# Wattuino-Uno_v10.net
KiCad netlist of a schematic drawn in EAGLE
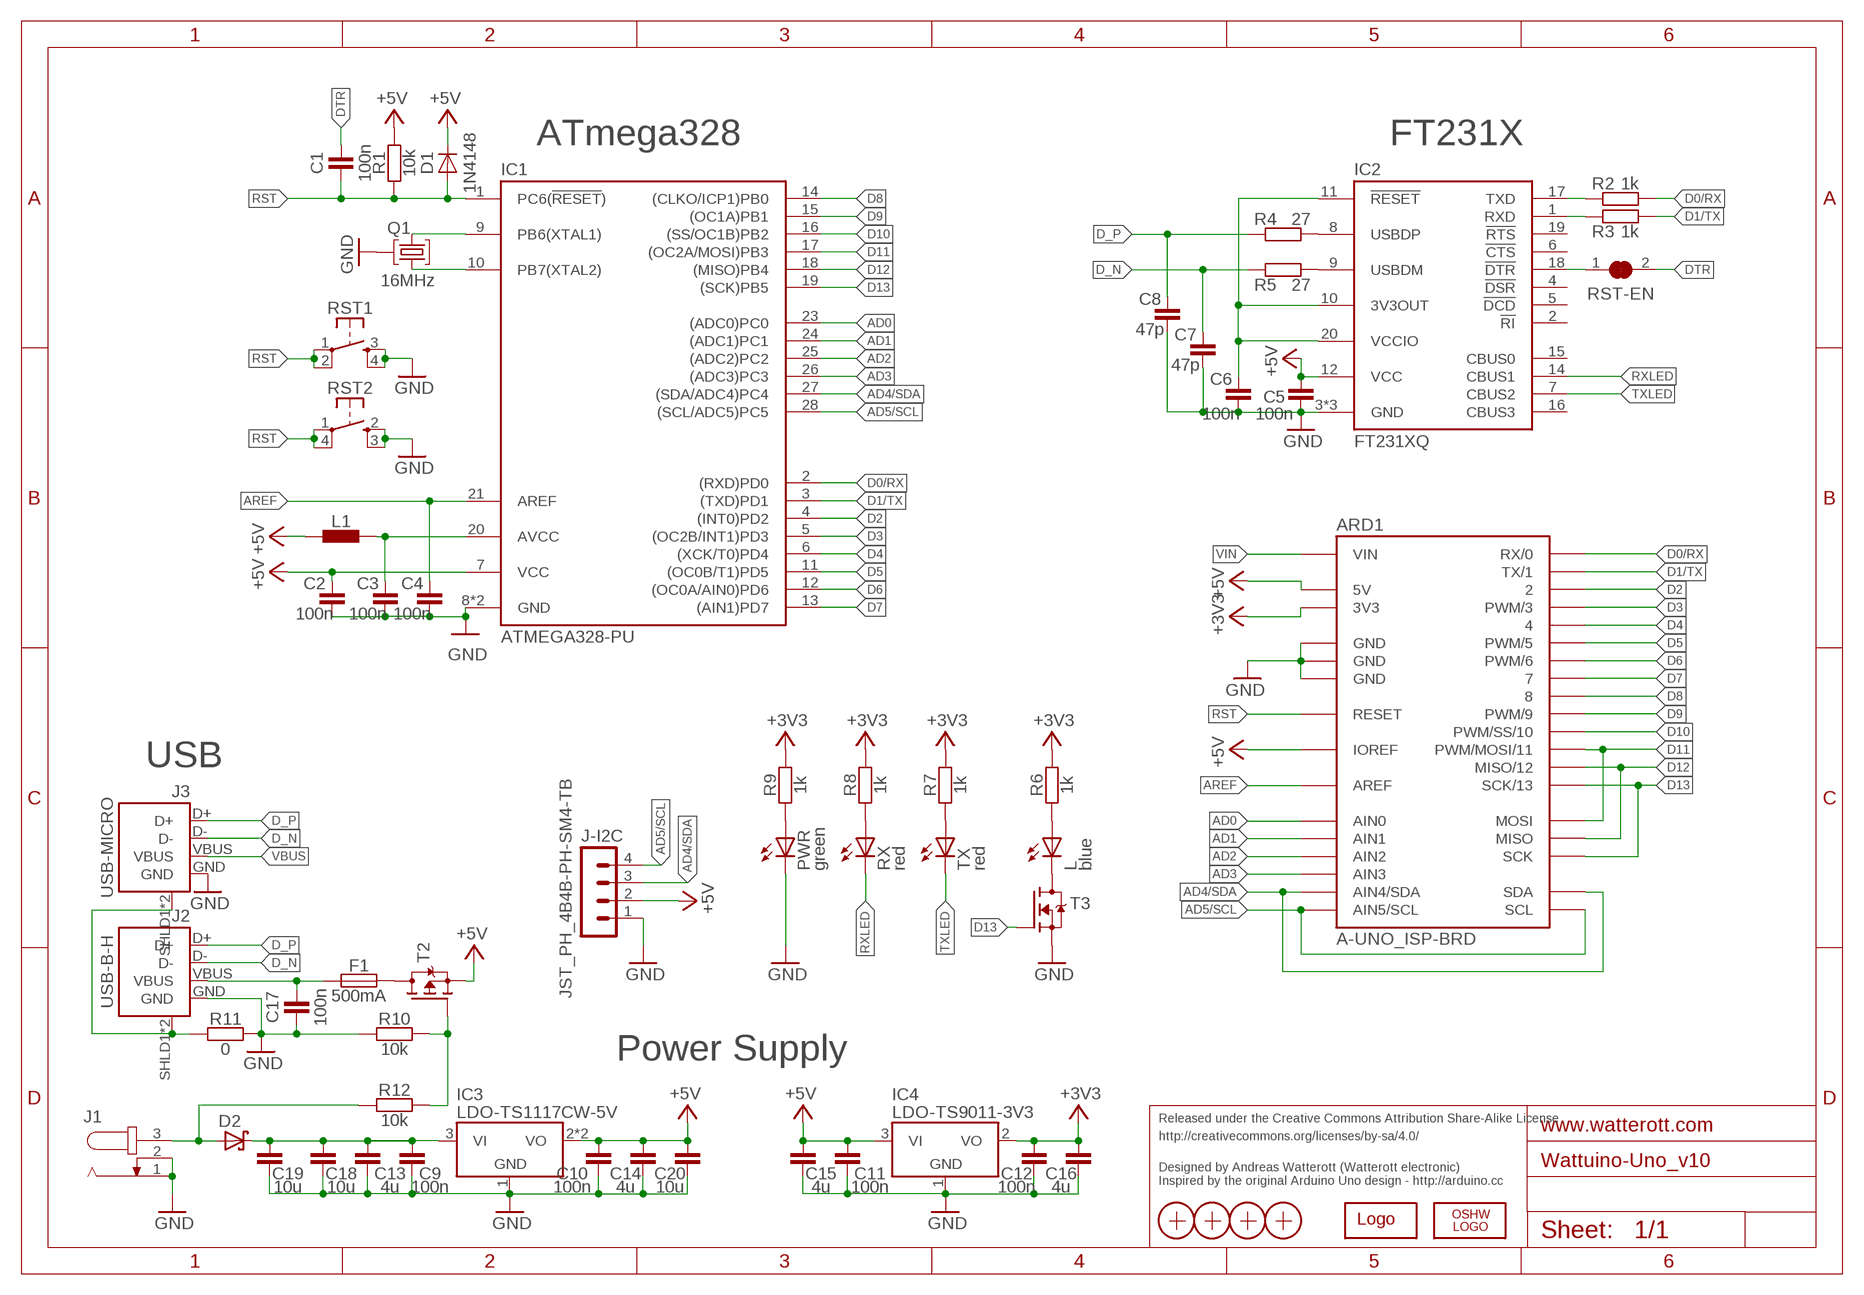
[diagram p0: schematic, sheet 1]

(export (version "E")
  (design (tool "Eeschema 10.0.6"))
  (components
    (comp (ref "ARD1")
      (value "A-UNO_ISP-BRD")
      (footprint "eagle-import:A-UNO-ISP")
      (libsource (lib "eagle-import") (part "A-UNO_ISP-BRD"))
    )
    (comp (ref "C1")
      (value "100n")
      (footprint "eagle-import:C0402")
      (libsource (lib "eagle-import") (part "CAPACITOR-0402"))
    )
    (comp (ref "C2")
      (value "100n")
      (footprint "eagle-import:C0402")
      (libsource (lib "eagle-import") (part "CAPACITOR-0402"))
    )
    (comp (ref "C3")
      (value "100n")
      (footprint "eagle-import:C0402")
      (libsource (lib "eagle-import") (part "CAPACITOR-0402"))
    )
    (comp (ref "C4")
      (value "100n")
      (footprint "eagle-import:C0402")
      (libsource (lib "eagle-import") (part "CAPACITOR-0402"))
    )
    (comp (ref "C5")
      (value "100n")
      (footprint "eagle-import:C0402")
      (libsource (lib "eagle-import") (part "CAPACITOR-0402"))
    )
    (comp (ref "C6")
      (value "100n")
      (footprint "eagle-import:C0402")
      (libsource (lib "eagle-import") (part "CAPACITOR-0402"))
    )
    (comp (ref "C7")
      (value "47p")
      (footprint "eagle-import:C0402")
      (libsource (lib "eagle-import") (part "CAPACITOR-0402"))
    )
    (comp (ref "C8")
      (value "47p")
      (footprint "eagle-import:C0402")
      (libsource (lib "eagle-import") (part "CAPACITOR-0402"))
    )
    (comp (ref "C9")
      (value "100n")
      (footprint "eagle-import:C0402")
      (libsource (lib "eagle-import") (part "CAPACITOR-0402"))
    )
    (comp (ref "C10")
      (value "100n")
      (footprint "eagle-import:C0402")
      (libsource (lib "eagle-import") (part "CAPACITOR-0402"))
    )
    (comp (ref "C11")
      (value "100n")
      (footprint "eagle-import:C0402")
      (libsource (lib "eagle-import") (part "CAPACITOR-0402"))
    )
    (comp (ref "C12")
      (value "100n")
      (footprint "eagle-import:C0402")
      (libsource (lib "eagle-import") (part "CAPACITOR-0402"))
    )
    (comp (ref "C13")
      (value "4u")
      (footprint "eagle-import:C0603")
      (libsource (lib "eagle-import") (part "CAPACITOR-0603"))
    )
    (comp (ref "C14")
      (value "4u")
      (footprint "eagle-import:C0603")
      (libsource (lib "eagle-import") (part "CAPACITOR-0603"))
    )
    (comp (ref "C15")
      (value "4u")
      (footprint "eagle-import:C0603")
      (libsource (lib "eagle-import") (part "CAPACITOR-0603"))
    )
    (comp (ref "C16")
      (value "4u")
      (footprint "eagle-import:C0603")
      (libsource (lib "eagle-import") (part "CAPACITOR-0603"))
    )
    (comp (ref "C17")
      (value "100n")
      (footprint "eagle-import:C0402")
      (libsource (lib "eagle-import") (part "CAPACITOR-0402"))
    )
    (comp (ref "C18")
      (value "10u")
      (footprint "eagle-import:C1206")
      (libsource (lib "eagle-import") (part "CAPACITOR-1206"))
    )
    (comp (ref "C19")
      (value "10u")
      (footprint "eagle-import:C1206")
      (libsource (lib "eagle-import") (part "CAPACITOR-1206"))
    )
    (comp (ref "C20")
      (value "10u")
      (footprint "eagle-import:C1206")
      (libsource (lib "eagle-import") (part "CAPACITOR-1206"))
    )
    (comp (ref "D1")
      (value "1N4148")
      (footprint "eagle-import:SOD110")
      (libsource (lib "eagle-import") (part "DIODE-SOD110"))
    )
    (comp (ref "D2")
      (value "D_SCHOTTKY-SS14")
      (footprint "eagle-import:SMA_DO214AC")
      (libsource (lib "eagle-import") (part "D_SCHOTTKY-SS14"))
    )
    (comp (ref "F1")
      (value "500mA")
      (footprint "eagle-import:C0805")
      (libsource (lib "eagle-import") (part "FUSE-0805"))
    )
    (comp (ref "IC1")
      (value "ATMEGA328-PU")
      (footprint "eagle-import:DIL28")
      (libsource (lib "eagle-import") (part "ATMEGA328-PU"))
    )
    (comp (ref "IC2")
      (value "FT231XQ")
      (footprint "eagle-import:QFN20-PAD")
      (libsource (lib "eagle-import") (part "FT231XQ"))
    )
    (comp (ref "IC3")
      (value "LDO-TS1117CW-5V")
      (footprint "eagle-import:SOT223")
      (libsource (lib "eagle-import") (part "LDO-TS1117CW-5V"))
    )
    (comp (ref "IC4")
      (value "LDO-TS9011-3V3")
      (footprint "eagle-import:SOT23")
      (libsource (lib "eagle-import") (part "LDO-TS9011-3V3"))
    )
    (comp (ref "J-I2C")
      (value "JST_PH_4B4B-PH-SM4-TB")
      (footprint "eagle-import:JST_B4B-PH-SM4-TB")
      (libsource (lib "eagle-import") (part "JST_PH_4B4B-PH-SM4-TB"))
    )
    (comp (ref "J1")
      (value "DC-JACK")
      (footprint "eagle-import:DC-JACK")
      (libsource (lib "eagle-import") (part "DC-JACK"))
    )
    (comp (ref "J2")
      (value "USB-B-H")
      (footprint "eagle-import:USB-B-H")
      (libsource (lib "eagle-import") (part "USB-B-H"))
    )
    (comp (ref "J3")
      (value "USB-MICRO")
      (footprint "eagle-import:USB-MICRO-10103594")
      (libsource (lib "eagle-import") (part "USB-MICRO"))
    )
    (comp (ref "L")
      (value "blue")
      (footprint "eagle-import:C0603")
      (libsource (lib "eagle-import") (part "LED-0603"))
    )
    (comp (ref "L1")
      (value "INDUCTOR-0603")
      (footprint "eagle-import:C0603")
      (libsource (lib "eagle-import") (part "INDUCTOR-0603"))
    )
    (comp (ref "LOGO1")
      (value "LOGO-S_PLACE_M")
      (footprint "eagle-import:SPARK_TPLACE_M")
      (libsource (lib "eagle-import") (part "LOGO-S_PLACE_M"))
    )
    (comp (ref "LOGO2")
      (value "OSHW_LOGOX0100")
      (footprint "eagle-import:OSHW_6X100")
      (libsource (lib "eagle-import") (part "OSHW_LOGOX0100"))
    )
    (comp (ref "PWR")
      (value "green")
      (footprint "eagle-import:C0603")
      (libsource (lib "eagle-import") (part "LED-0603"))
    )
    (comp (ref "Q1")
      (value "16MHz")
      (footprint "eagle-import:CRYSTAL_32X13")
      (libsource (lib "eagle-import") (part "CRYSTAL-RES-32"))
    )
    (comp (ref "R1")
      (value "10k")
      (footprint "eagle-import:C0402")
      (libsource (lib "eagle-import") (part "RESISTOR-0402"))
    )
    (comp (ref "R2")
      (value "1k")
      (footprint "eagle-import:C0402")
      (libsource (lib "eagle-import") (part "RESISTOR-0402"))
    )
    (comp (ref "R3")
      (value "1k")
      (footprint "eagle-import:C0402")
      (libsource (lib "eagle-import") (part "RESISTOR-0402"))
    )
    (comp (ref "R4")
      (value "27")
      (footprint "eagle-import:C0402")
      (libsource (lib "eagle-import") (part "RESISTOR-0402"))
    )
    (comp (ref "R5")
      (value "27")
      (footprint "eagle-import:C0402")
      (libsource (lib "eagle-import") (part "RESISTOR-0402"))
    )
    (comp (ref "R6")
      (value "1k")
      (footprint "eagle-import:C0402")
      (libsource (lib "eagle-import") (part "RESISTOR-0402"))
    )
    (comp (ref "R7")
      (value "1k")
      (footprint "eagle-import:C0402")
      (libsource (lib "eagle-import") (part "RESISTOR-0402"))
    )
    (comp (ref "R8")
      (value "1k")
      (footprint "eagle-import:C0402")
      (libsource (lib "eagle-import") (part "RESISTOR-0402"))
    )
    (comp (ref "R9")
      (value "1k")
      (footprint "eagle-import:C0402")
      (libsource (lib "eagle-import") (part "RESISTOR-0402"))
    )
    (comp (ref "R10")
      (value "10k")
      (footprint "eagle-import:C0402")
      (libsource (lib "eagle-import") (part "RESISTOR-0402"))
    )
    (comp (ref "R11")
      (value "0")
      (footprint "eagle-import:C0402")
      (libsource (lib "eagle-import") (part "RESISTOR-0402"))
    )
    (comp (ref "R12")
      (value "10k")
      (footprint "eagle-import:C0402")
      (libsource (lib "eagle-import") (part "RESISTOR-0402"))
    )
    (comp (ref "RST-EN")
      (value "JUMPER2-0603")
      (footprint "eagle-import:JUMPER2-0603")
      (libsource (lib "eagle-import") (part "JUMPER2-0603"))
    )
    (comp (ref "RST1")
      (value "SW-TACTILE-PTS840P")
      (footprint "eagle-import:SW_PTS840P")
      (libsource (lib "eagle-import") (part "SW-TACTILE-PTS840P"))
    )
    (comp (ref "RST2")
      (value "SW-TACTILE-TL3315")
      (footprint "eagle-import:SW_TL3315N")
      (libsource (lib "eagle-import") (part "SW-TACTILE-TL3315"))
    )
    (comp (ref "RX")
      (value "red")
      (footprint "eagle-import:C0603")
      (libsource (lib "eagle-import") (part "LED-0603"))
    )
    (comp (ref "T2")
      (value "MOSFET-P-SOT23")
      (footprint "eagle-import:SOT23")
      (libsource (lib "eagle-import") (part "MOSFET-P-SOT23"))
    )
    (comp (ref "T3")
      (value "MOSFET-N-SOT23")
      (footprint "eagle-import:SOT23")
      (libsource (lib "eagle-import") (part "MOSFET-N-SOT23"))
    )
    (comp (ref "TX")
      (value "red")
      (footprint "eagle-import:C0603")
      (libsource (lib "eagle-import") (part "LED-0603"))
    )
    (comp (ref "X1")
      (value "PASSER-07")
      (footprint "eagle-import:PASSER_07MM")
      (libsource (lib "eagle-import") (part "PASSER-07"))
    )
    (comp (ref "X2")
      (value "PASSER-07")
      (footprint "eagle-import:PASSER_07MM")
      (libsource (lib "eagle-import") (part "PASSER-07"))
    )
    (comp (ref "X3")
      (value "PASSER-07")
      (footprint "eagle-import:PASSER_07MM")
      (libsource (lib "eagle-import") (part "PASSER-07"))
    )
    (comp (ref "X4")
      (value "PASSER-07")
      (footprint "eagle-import:PASSER_07MM")
      (libsource (lib "eagle-import") (part "PASSER-07"))
    )
  )
  (nets
    (net (code "1") (name "+3V3") (class "Default")
      (node (ref "ARD1") (pin "3V3") (pinfunction "3V3_3V3") (pintype "power_in"))
      (node (ref "C12") (pin "2") (pinfunction "2_2") (pintype "passive"))
      (node (ref "C16") (pin "2") (pinfunction "2_2") (pintype "passive"))
      (node (ref "IC4") (pin "2") (pinfunction "VO_2") (pintype "passive"))
      (node (ref "R6") (pin "2") (pinfunction "2_2") (pintype "passive"))
      (node (ref "R7") (pin "2") (pinfunction "2_2") (pintype "passive"))
      (node (ref "R8") (pin "2") (pinfunction "2_2") (pintype "passive"))
      (node (ref "R9") (pin "2") (pinfunction "2_2") (pintype "passive"))
    )
    (net (code "2") (name "+5V") (class "Default")
      (node (ref "ARD1") (pin "5V") (pinfunction "5V_5V") (pintype "power_in"))
      (node (ref "ARD1") (pin "IOREF") (pinfunction "IOREF_IOREF") (pintype "power_in"))
      (node (ref "ARD1") (pin "VCC") (pinfunction "5V_VCC") (pintype "power_in"))
      (node (ref "C10") (pin "2") (pinfunction "2_2") (pintype "passive"))
      (node (ref "C11") (pin "2") (pinfunction "2_2") (pintype "passive"))
      (node (ref "C14") (pin "2") (pinfunction "2_2") (pintype "passive"))
      (node (ref "C15") (pin "2") (pinfunction "2_2") (pintype "passive"))
      (node (ref "C2") (pin "2") (pinfunction "2_2") (pintype "passive"))
      (node (ref "C20") (pin "2") (pinfunction "2_2") (pintype "passive"))
      (node (ref "C5") (pin "2") (pinfunction "2_2") (pintype "passive"))
      (node (ref "D1") (pin "C") (pinfunction "C_C") (pintype "passive"))
      (node (ref "IC1") (pin "7") (pinfunction "VCC_7") (pintype "power_in"))
      (node (ref "IC2") (pin "12") (pinfunction "VCC_12") (pintype "power_in"))
      (node (ref "IC3") (pin "2") (pinfunction "VO_2") (pintype "passive"))
      (node (ref "IC3") (pin "4") (pinfunction "VO_4") (pintype "passive"))
      (node (ref "IC4") (pin "3") (pinfunction "VI_3") (pintype "input"))
      (node (ref "J-I2C") (pin "2") (pinfunction "2_2") (pintype "passive"))
      (node (ref "L1") (pin "1") (pinfunction "1_1") (pintype "passive"))
      (node (ref "R1") (pin "2") (pinfunction "2_2") (pintype "passive"))
      (node (ref "T2") (pin "2") (pinfunction "S_2") (pintype "passive"))
    )
    (net (code "3") (name "AD0") (class "Default")
      (node (ref "ARD1") (pin "A0") (pinfunction "AIN0_A0") (pintype "bidirectional"))
      (node (ref "IC1") (pin "23") (pinfunction "(ADC0)PC0_23") (pintype "bidirectional"))
    )
    (net (code "4") (name "AD1") (class "Default")
      (node (ref "ARD1") (pin "A1") (pinfunction "AIN1_A1") (pintype "bidirectional"))
      (node (ref "IC1") (pin "24") (pinfunction "(ADC1)PC1_24") (pintype "bidirectional"))
    )
    (net (code "5") (name "AD2") (class "Default")
      (node (ref "ARD1") (pin "A2") (pinfunction "AIN2_A2") (pintype "bidirectional"))
      (node (ref "IC1") (pin "25") (pinfunction "(ADC2)PC2_25") (pintype "bidirectional"))
    )
    (net (code "6") (name "AD3") (class "Default")
      (node (ref "ARD1") (pin "A3") (pinfunction "AIN3_A3") (pintype "bidirectional"))
      (node (ref "IC1") (pin "26") (pinfunction "(ADC3)PC3_26") (pintype "bidirectional"))
    )
    (net (code "7") (name "AD4{slash}SDA") (class "Default")
      (node (ref "ARD1") (pin "A4") (pinfunction "AIN4/SDA_A4") (pintype "bidirectional"))
      (node (ref "ARD1") (pin "SDA") (pinfunction "SDA_SDA") (pintype "bidirectional"))
      (node (ref "IC1") (pin "27") (pinfunction "(SDA/ADC4)PC4_27") (pintype "bidirectional"))
      (node (ref "J-I2C") (pin "3") (pinfunction "3_3") (pintype "passive"))
    )
    (net (code "8") (name "AD5{slash}SCL") (class "Default")
      (node (ref "ARD1") (pin "A5") (pinfunction "AIN5/SCL_A5") (pintype "bidirectional"))
      (node (ref "ARD1") (pin "SCL") (pinfunction "SCL_SCL") (pintype "bidirectional"))
      (node (ref "IC1") (pin "28") (pinfunction "(SCL/ADC5)PC5_28") (pintype "bidirectional"))
      (node (ref "J-I2C") (pin "4") (pinfunction "4_4") (pintype "passive"))
    )
    (net (code "9") (name "AREF") (class "Default")
      (node (ref "ARD1") (pin "AREF") (pinfunction "AREF_AREF") (pintype "power_in"))
      (node (ref "C4") (pin "2") (pinfunction "2_2") (pintype "passive"))
      (node (ref "IC1") (pin "21") (pinfunction "AREF_21") (pintype "passive"))
    )
    (net (code "10") (name "D0{slash}RX") (class "Default")
      (node (ref "ARD1") (pin "0") (pinfunction "RX/0_0") (pintype "bidirectional"))
      (node (ref "IC1") (pin "2") (pinfunction "(RXD)PD0_2") (pintype "bidirectional"))
      (node (ref "R2") (pin "2") (pinfunction "2_2") (pintype "passive"))
    )
    (net (code "11") (name "D1{slash}TX") (class "Default")
      (node (ref "ARD1") (pin "1") (pinfunction "TX/1_1") (pintype "bidirectional"))
      (node (ref "IC1") (pin "3") (pinfunction "(TXD)PD1_3") (pintype "bidirectional"))
      (node (ref "R3") (pin "2") (pinfunction "2_2") (pintype "passive"))
    )
    (net (code "12") (name "D2") (class "Default")
      (node (ref "ARD1") (pin "2") (pinfunction "2_2") (pintype "bidirectional"))
      (node (ref "IC1") (pin "4") (pinfunction "(INT0)PD2_4") (pintype "bidirectional"))
    )
    (net (code "13") (name "D3") (class "Default")
      (node (ref "ARD1") (pin "3") (pinfunction "PWM/3_3") (pintype "bidirectional"))
      (node (ref "IC1") (pin "5") (pinfunction "(OC2B/INT1)PD3_5") (pintype "bidirectional"))
    )
    (net (code "14") (name "D4") (class "Default")
      (node (ref "ARD1") (pin "4") (pinfunction "4_4") (pintype "bidirectional"))
      (node (ref "IC1") (pin "6") (pinfunction "(XCK/T0)PD4_6") (pintype "bidirectional"))
    )
    (net (code "15") (name "D5") (class "Default")
      (node (ref "ARD1") (pin "5") (pinfunction "PWM/5_5") (pintype "bidirectional"))
      (node (ref "IC1") (pin "11") (pinfunction "(OC0B/T1)PD5_11") (pintype "bidirectional"))
    )
    (net (code "16") (name "D6") (class "Default")
      (node (ref "ARD1") (pin "6") (pinfunction "PWM/6_6") (pintype "bidirectional"))
      (node (ref "IC1") (pin "12") (pinfunction "(OC0A/AIN0)PD6_12") (pintype "bidirectional"))
    )
    (net (code "17") (name "D7") (class "Default")
      (node (ref "ARD1") (pin "7") (pinfunction "7_7") (pintype "bidirectional"))
      (node (ref "IC1") (pin "13") (pinfunction "(AIN1)PD7_13") (pintype "bidirectional"))
    )
    (net (code "18") (name "D8") (class "Default")
      (node (ref "ARD1") (pin "8") (pinfunction "8_8") (pintype "bidirectional"))
      (node (ref "IC1") (pin "14") (pinfunction "(CLKO/ICP1)PB0_14") (pintype "bidirectional"))
    )
    (net (code "19") (name "D9") (class "Default")
      (node (ref "ARD1") (pin "9") (pinfunction "PWM/9_9") (pintype "bidirectional"))
      (node (ref "IC1") (pin "15") (pinfunction "(OC1A)PB1_15") (pintype "bidirectional"))
    )
    (net (code "20") (name "D10") (class "Default")
      (node (ref "ARD1") (pin "10") (pinfunction "PWM/SS/10_10") (pintype "bidirectional"))
      (node (ref "IC1") (pin "16") (pinfunction "(SS/OC1B)PB2_16") (pintype "bidirectional"))
    )
    (net (code "21") (name "D11") (class "Default")
      (node (ref "ARD1") (pin "11") (pinfunction "PWM/MOSI/11_11") (pintype "bidirectional"))
      (node (ref "ARD1") (pin "MOSI") (pinfunction "MOSI_MOSI") (pintype "bidirectional"))
      (node (ref "IC1") (pin "17") (pinfunction "(OC2A/MOSI)PB3_17") (pintype "bidirectional"))
    )
    (net (code "22") (name "D12") (class "Default")
      (node (ref "ARD1") (pin "12") (pinfunction "MISO/12_12") (pintype "bidirectional"))
      (node (ref "ARD1") (pin "MISO") (pinfunction "MISO_MISO") (pintype "bidirectional"))
      (node (ref "IC1") (pin "18") (pinfunction "(MISO)PB4_18") (pintype "bidirectional"))
    )
    (net (code "23") (name "D13") (class "Default")
      (node (ref "ARD1") (pin "13") (pinfunction "SCK/13_13") (pintype "bidirectional"))
      (node (ref "ARD1") (pin "SCK") (pinfunction "SCK_SCK") (pintype "bidirectional"))
      (node (ref "IC1") (pin "19") (pinfunction "(SCK)PB5_19") (pintype "bidirectional"))
      (node (ref "T3") (pin "1") (pinfunction "G_1") (pintype "passive"))
    )
    (net (code "24") (name "DTR") (class "Default")
      (node (ref "C1") (pin "2") (pinfunction "2_2") (pintype "passive"))
      (node (ref "RST-EN") (pin "2") (pinfunction "2_2") (pintype "passive"))
    )
    (net (code "25") (name "D_N") (class "Default")
      (node (ref "C7") (pin "2") (pinfunction "2_2") (pintype "passive"))
      (node (ref "J2") (pin "D-") (pinfunction "D-_D-") (pintype "bidirectional"))
      (node (ref "J3") (pin "D-") (pinfunction "D-_D-") (pintype "bidirectional"))
      (node (ref "R5") (pin "1") (pinfunction "1_1") (pintype "passive"))
    )
    (net (code "26") (name "D_P") (class "Default")
      (node (ref "C8") (pin "2") (pinfunction "2_2") (pintype "passive"))
      (node (ref "J2") (pin "D+") (pinfunction "D+_D+") (pintype "bidirectional"))
      (node (ref "J3") (pin "D+") (pinfunction "D+_D+") (pintype "bidirectional"))
      (node (ref "R4") (pin "1") (pinfunction "1_1") (pintype "passive"))
    )
    (net (code "27") (name "GND") (class "Default")
      (node (ref "ARD1") (pin "GND@1") (pinfunction "GND_GND@1") (pintype "power_in"))
      (node (ref "ARD1") (pin "GND@2") (pinfunction "GND_GND@2") (pintype "power_in"))
      (node (ref "ARD1") (pin "GND@3") (pinfunction "GND_GND@3") (pintype "power_in"))
      (node (ref "ARD1") (pin "GND@4") (pinfunction "GND_GND@4") (pintype "power_in"))
      (node (ref "C10") (pin "1") (pinfunction "1_1") (pintype "passive"))
      (node (ref "C11") (pin "1") (pinfunction "1_1") (pintype "passive"))
      (node (ref "C12") (pin "1") (pinfunction "1_1") (pintype "passive"))
      (node (ref "C13") (pin "1") (pinfunction "1_1") (pintype "passive"))
      (node (ref "C14") (pin "1") (pinfunction "1_1") (pintype "passive"))
      (node (ref "C15") (pin "1") (pinfunction "1_1") (pintype "passive"))
      (node (ref "C16") (pin "1") (pinfunction "1_1") (pintype "passive"))
      (node (ref "C17") (pin "1") (pinfunction "1_1") (pintype "passive"))
      (node (ref "C18") (pin "1") (pinfunction "1_1") (pintype "passive"))
      (node (ref "C19") (pin "1") (pinfunction "1_1") (pintype "passive"))
      (node (ref "C2") (pin "1") (pinfunction "1_1") (pintype "passive"))
      (node (ref "C20") (pin "1") (pinfunction "1_1") (pintype "passive"))
      (node (ref "C3") (pin "1") (pinfunction "1_1") (pintype "passive"))
      (node (ref "C4") (pin "1") (pinfunction "1_1") (pintype "passive"))
      (node (ref "C5") (pin "1") (pinfunction "1_1") (pintype "passive"))
      (node (ref "C6") (pin "1") (pinfunction "1_1") (pintype "passive"))
      (node (ref "C7") (pin "1") (pinfunction "1_1") (pintype "passive"))
      (node (ref "C8") (pin "1") (pinfunction "1_1") (pintype "passive"))
      (node (ref "C9") (pin "1") (pinfunction "1_1") (pintype "passive"))
      (node (ref "IC1") (pin "22") (pinfunction "GND_22") (pintype "power_in"))
      (node (ref "IC1") (pin "8") (pinfunction "GND_8") (pintype "power_in"))
      (node (ref "IC2") (pin "13") (pinfunction "GND_13") (pintype "power_in"))
      (node (ref "IC2") (pin "3") (pinfunction "GND_3") (pintype "power_in"))
      (node (ref "IC2") (pin "TP") (pinfunction "GND_TP") (pintype "power_in"))
      (node (ref "IC3") (pin "1") (pinfunction "GND_1") (pintype "passive"))
      (node (ref "IC4") (pin "1") (pinfunction "GND_1") (pintype "passive"))
      (node (ref "J-I2C") (pin "1") (pinfunction "1_1") (pintype "passive"))
      (node (ref "J1") (pin "1") (pinfunction "1_1") (pintype "passive"))
      (node (ref "J1") (pin "2") (pinfunction "2_2") (pintype "passive"))
      (node (ref "J2") (pin "GND") (pinfunction "GND_GND") (pintype "power_in"))
      (node (ref "J3") (pin "GND") (pinfunction "GND_GND") (pintype "power_in"))
      (node (ref "PWR") (pin "C") (pinfunction "C_C") (pintype "passive"))
      (node (ref "Q1") (pin "GND") (pinfunction "GND_GND") (pintype "passive"))
      (node (ref "R10") (pin "1") (pinfunction "1_1") (pintype "passive"))
      (node (ref "R11") (pin "2") (pinfunction "2_2") (pintype "passive"))
      (node (ref "RST1") (pin "3") (pinfunction "S1_3") (pintype "passive"))
      (node (ref "RST1") (pin "4") (pinfunction "S2_4") (pintype "passive"))
      (node (ref "RST2") (pin "2") (pinfunction "S1_2") (pintype "passive"))
      (node (ref "RST2") (pin "3") (pinfunction "S2_3") (pintype "passive"))
      (node (ref "T3") (pin "2") (pinfunction "S_2") (pintype "passive"))
    )
    (net (code "28") (name "Net-(D2-PadA)") (class "Default")
      (node (ref "D2") (pin "A") (pinfunction "A_A") (pintype "passive"))
      (node (ref "J1") (pin "3") (pinfunction "3_3") (pintype "passive"))
      (node (ref "R12") (pin "1") (pinfunction "1_1") (pintype "passive"))
    )
    (net (code "29") (name "Net-(IC1-AVCC)") (class "Default")
      (node (ref "C3") (pin "2") (pinfunction "2_2") (pintype "passive"))
      (node (ref "IC1") (pin "20") (pinfunction "AVCC_20") (pintype "power_in"))
      (node (ref "L1") (pin "2") (pinfunction "2_2") (pintype "passive"))
    )
    (net (code "30") (name "Net-(IC1-PB6(XTAL1))") (class "Default")
      (node (ref "IC1") (pin "9") (pinfunction "PB6(XTAL1)_9") (pintype "bidirectional"))
      (node (ref "Q1") (pin "2") (pinfunction "2_2") (pintype "passive"))
    )
    (net (code "31") (name "Net-(IC1-PB7(XTAL2))") (class "Default")
      (node (ref "IC1") (pin "10") (pinfunction "PB7(XTAL2)_10") (pintype "bidirectional"))
      (node (ref "Q1") (pin "1") (pinfunction "1_1") (pintype "passive"))
    )
    (net (code "32") (name "Net-(IC2-3V3OUT)") (class "Default")
      (node (ref "C6") (pin "2") (pinfunction "2_2") (pintype "passive"))
      (node (ref "IC2") (pin "10") (pinfunction "3V3OUT_10") (pintype "power_in"))
      (node (ref "IC2") (pin "11") (pinfunction "~{RESET}_11") (pintype "bidirectional"))
      (node (ref "IC2") (pin "20") (pinfunction "VCCIO_20") (pintype "power_in"))
    )
    (net (code "33") (name "Net-(IC2-RXD)") (class "Default")
      (node (ref "IC2") (pin "1") (pinfunction "RXD_1") (pintype "bidirectional"))
      (node (ref "R3") (pin "1") (pinfunction "1_1") (pintype "passive"))
    )
    (net (code "34") (name "Net-(IC2-TXD)") (class "Default")
      (node (ref "IC2") (pin "17") (pinfunction "TXD_17") (pintype "bidirectional"))
      (node (ref "R2") (pin "1") (pinfunction "1_1") (pintype "passive"))
    )
    (net (code "35") (name "Net-(IC2-USBDM)") (class "Default")
      (node (ref "IC2") (pin "9") (pinfunction "USBDM_9") (pintype "bidirectional"))
      (node (ref "R5") (pin "2") (pinfunction "2_2") (pintype "passive"))
    )
    (net (code "36") (name "Net-(IC2-USBDP)") (class "Default")
      (node (ref "IC2") (pin "8") (pinfunction "USBDP_8") (pintype "bidirectional"))
      (node (ref "R4") (pin "2") (pinfunction "2_2") (pintype "passive"))
    )
    (net (code "37") (name "Net-(IC2-~{DTR})") (class "Default")
      (node (ref "IC2") (pin "18") (pinfunction "~{DTR}_18") (pintype "bidirectional"))
      (node (ref "RST-EN") (pin "1") (pinfunction "1_1") (pintype "passive"))
    )
    (net (code "38") (name "Net-(J2-SHIELD-PadSHLD1)") (class "Default")
      (node (ref "J2") (pin "SHLD1") (pinfunction "SHIELD_SHLD1") (pintype "passive"))
      (node (ref "J2") (pin "SHLD2") (pinfunction "SHIELD_SHLD2") (pintype "passive"))
      (node (ref "J3") (pin "SHLD1") (pinfunction "SHIELD_SHLD1") (pintype "passive"))
      (node (ref "J3") (pin "SHLD2") (pinfunction "SHIELD_SHLD2") (pintype "passive"))
      (node (ref "R11") (pin "1") (pinfunction "1_1") (pintype "passive"))
    )
    (net (code "39") (name "Net-(L-PadA)") (class "Default")
      (node (ref "L") (pin "A") (pinfunction "A_A") (pintype "passive"))
      (node (ref "R6") (pin "1") (pinfunction "1_1") (pintype "passive"))
    )
    (net (code "40") (name "Net-(PWR-PadA)") (class "Default")
      (node (ref "PWR") (pin "A") (pinfunction "A_A") (pintype "passive"))
      (node (ref "R9") (pin "1") (pinfunction "1_1") (pintype "passive"))
    )
    (net (code "41") (name "Net-(R7-Pad1)") (class "Default")
      (node (ref "R7") (pin "1") (pinfunction "1_1") (pintype "passive"))
      (node (ref "TX") (pin "A") (pinfunction "A_A") (pintype "passive"))
    )
    (net (code "42") (name "Net-(R8-Pad1)") (class "Default")
      (node (ref "R8") (pin "1") (pinfunction "1_1") (pintype "passive"))
      (node (ref "RX") (pin "A") (pinfunction "A_A") (pintype "passive"))
    )
    (net (code "43") (name "Net-(T2-D)") (class "Default")
      (node (ref "F1") (pin "2") (pinfunction "2_2") (pintype "passive"))
      (node (ref "T2") (pin "3") (pinfunction "D_3") (pintype "passive"))
    )
    (net (code "44") (name "Net-(T2-G)") (class "Default")
      (node (ref "R10") (pin "2") (pinfunction "2_2") (pintype "passive"))
      (node (ref "R12") (pin "2") (pinfunction "2_2") (pintype "passive"))
      (node (ref "T2") (pin "1") (pinfunction "G_1") (pintype "passive"))
    )
    (net (code "45") (name "Net-(T3-D)") (class "Default")
      (node (ref "L") (pin "C") (pinfunction "C_C") (pintype "passive"))
      (node (ref "T3") (pin "3") (pinfunction "D_3") (pintype "passive"))
    )
    (net (code "46") (name "RST") (class "Default")
      (node (ref "ARD1") (pin "RST") (pinfunction "RESET_RST") (pintype "bidirectional"))
      (node (ref "ARD1") (pin "RST2") (pinfunction "RESET_RST2") (pintype "bidirectional"))
      (node (ref "C1") (pin "1") (pinfunction "1_1") (pintype "passive"))
      (node (ref "D1") (pin "A") (pinfunction "A_A") (pintype "passive"))
      (node (ref "IC1") (pin "1") (pinfunction "PC6(~{RESET})_1") (pintype "bidirectional"))
      (node (ref "R1") (pin "1") (pinfunction "1_1") (pintype "passive"))
      (node (ref "RST1") (pin "1") (pinfunction "P1_1") (pintype "passive"))
      (node (ref "RST1") (pin "2") (pinfunction "P2_2") (pintype "passive"))
      (node (ref "RST2") (pin "1") (pinfunction "P1_1") (pintype "passive"))
      (node (ref "RST2") (pin "4") (pinfunction "P2_4") (pintype "passive"))
    )
    (net (code "47") (name "RXLED") (class "Default")
      (node (ref "IC2") (pin "14") (pinfunction "CBUS1_14") (pintype "bidirectional"))
      (node (ref "RX") (pin "C") (pinfunction "C_C") (pintype "passive"))
    )
    (net (code "48") (name "TXLED") (class "Default")
      (node (ref "IC2") (pin "7") (pinfunction "CBUS2_7") (pintype "bidirectional"))
      (node (ref "TX") (pin "C") (pinfunction "C_C") (pintype "passive"))
    )
    (net (code "49") (name "VBUS") (class "Default")
      (node (ref "C17") (pin "2") (pinfunction "2_2") (pintype "passive"))
      (node (ref "F1") (pin "1") (pinfunction "1_1") (pintype "passive"))
      (node (ref "J2") (pin "VBUS") (pinfunction "VBUS_VBUS") (pintype "power_in"))
      (node (ref "J3") (pin "VBUS") (pinfunction "VBUS_VBUS") (pintype "power_in"))
    )
    (net (code "50") (name "VIN") (class "Default")
      (node (ref "ARD1") (pin "VIN") (pinfunction "VIN_VIN") (pintype "power_in"))
      (node (ref "C13") (pin "2") (pinfunction "2_2") (pintype "passive"))
      (node (ref "C18") (pin "2") (pinfunction "2_2") (pintype "passive"))
      (node (ref "C19") (pin "2") (pinfunction "2_2") (pintype "passive"))
      (node (ref "C9") (pin "2") (pinfunction "2_2") (pintype "passive"))
      (node (ref "D2") (pin "C") (pinfunction "C_C") (pintype "passive"))
      (node (ref "IC3") (pin "3") (pinfunction "VI_3") (pintype "input"))
    )
    (net (code "51") (name "unconnected-(IC2-CBUS0-Pad15)") (class "Default")
      (node (ref "IC2") (pin "15") (pinfunction "CBUS0_15") (pintype "bidirectional"))
    )
    (net (code "52") (name "unconnected-(IC2-CBUS3-Pad16)") (class "Default")
      (node (ref "IC2") (pin "16") (pinfunction "CBUS3_16") (pintype "bidirectional"))
    )
    (net (code "53") (name "unconnected-(IC2-~{CTS}-Pad6)") (class "Default")
      (node (ref "IC2") (pin "6") (pinfunction "~{CTS}_6") (pintype "bidirectional"))
    )
    (net (code "54") (name "unconnected-(IC2-~{DCD}-Pad5)") (class "Default")
      (node (ref "IC2") (pin "5") (pinfunction "~{DCD}_5") (pintype "bidirectional"))
    )
    (net (code "55") (name "unconnected-(IC2-~{DSR}-Pad4)") (class "Default")
      (node (ref "IC2") (pin "4") (pinfunction "~{DSR}_4") (pintype "bidirectional"))
    )
    (net (code "56") (name "unconnected-(IC2-~{RI}-Pad2)") (class "Default")
      (node (ref "IC2") (pin "2") (pinfunction "~{RI}_2") (pintype "bidirectional"))
    )
    (net (code "57") (name "unconnected-(IC2-~{RTS}-Pad19)") (class "Default")
      (node (ref "IC2") (pin "19") (pinfunction "~{RTS}_19") (pintype "bidirectional"))
    )
  )
)
